# Main.net
KiCad netlist of a schematic drawn in Altium Designer
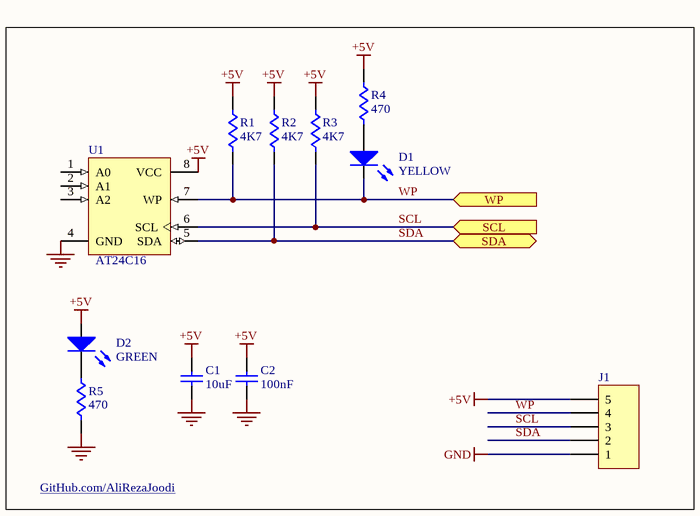
[diagram p0: Main.SchDoc]

(export (version "E")
  (design (tool "Eeschema 10.0.6"))
  (components
    (comp (ref "C1")
      (value "10uF")
      (footprint "0805")
      (description "Capacitor")
      (fields (field (name "MANUFACTURER") "Generic Components") (field (name "PUBLISHER") "Altium Limited"))
      (libsource (lib "Miscellaneous Devices") (part "Cap"))
    )
    (comp (ref "C2")
      (value "100nF")
      (footprint "0805")
      (description "Capacitor")
      (fields (field (name "MANUFACTURER") "Generic Components") (field (name "PUBLISHER") "Altium Limited"))
      (libsource (lib "Miscellaneous Devices") (part "Cap"))
    )
    (comp (ref "D1")
      (value "YELLOW")
      (footprint "0805_Diode")
      (description "Typical INFRARED GaAs LED")
      (fields (field (name "MANUFACTURER") "Generic Components") (field (name "PUBLISHER") "Altium Limited"))
      (libsource (lib "Miscellaneous Devices") (part "LED"))
    )
    (comp (ref "D2")
      (value "GREEN")
      (footprint "0805_Diode")
      (description "Typical INFRARED GaAs LED")
      (fields (field (name "MANUFACTURER") "Generic Components") (field (name "PUBLISHER") "Altium Limited"))
      (libsource (lib "Miscellaneous Devices") (part "LED"))
    )
    (comp (ref "J1")
      (value "5PIN")
      (footprint "HDR1X5")
      (description "Header, 5-Pin")
      (fields (field (name "MANUFACTURER") "Generic Components") (field (name "PUBLISHER") "Altium Limited"))
      (libsource (lib "Miscellaneous Connectors") (part "Header 5"))
    )
    (comp (ref "R1")
      (value "4K7")
      (footprint "0805")
      (description "Resistor")
      (fields (field (name "MANUFACTURER") "Generic Components") (field (name "PUBLISHER") "Altium Limited"))
      (libsource (lib "Miscellaneous Devices") (part "Res1"))
    )
    (comp (ref "R2")
      (value "4K7")
      (footprint "0805")
      (description "Resistor")
      (fields (field (name "MANUFACTURER") "Generic Components") (field (name "PUBLISHER") "Altium Limited"))
      (libsource (lib "Miscellaneous Devices") (part "Res1"))
    )
    (comp (ref "R3")
      (value "4K7")
      (footprint "0805")
      (description "Resistor")
      (fields (field (name "MANUFACTURER") "Generic Components") (field (name "PUBLISHER") "Altium Limited"))
      (libsource (lib "Miscellaneous Devices") (part "Res1"))
    )
    (comp (ref "R4")
      (value "470")
      (footprint "0805")
      (description "Resistor")
      (fields (field (name "MANUFACTURER") "Generic Components") (field (name "PUBLISHER") "Altium Limited"))
      (libsource (lib "Miscellaneous Devices") (part "Res1"))
    )
    (comp (ref "R5")
      (value "470")
      (footprint "0805")
      (description "Resistor")
      (fields (field (name "MANUFACTURER") "Generic Components") (field (name "PUBLISHER") "Altium Limited"))
      (libsource (lib "Miscellaneous Devices") (part "Res1"))
    )
    (comp (ref "U1")
      (value "AT24C16")
      (footprint "SOP127P636-8N")
      (description "1Kbit (128 x 8), 2-wire Bus Automotive Serial EEPROM with Write Protect, 2.5V, 8-Pin TSSOP, Bulk")
      (fields (field (name "PUBLISHER") "Altium Limited"))
      (libsource (lib "Atmel Memory Serial EEPROM") (part "AT24C01B-TP25-B"))
    )
  )
  (nets
    (net (code "1") (name "+5V") (class "Default")
      (node (ref "C1") (pin "2") (pinfunction "2_2") (pintype "passive"))
      (node (ref "C2") (pin "2") (pinfunction "2_2") (pintype "passive"))
      (node (ref "D2") (pin "1") (pinfunction "A_1") (pintype "passive"))
      (node (ref "J1") (pin "5") (pinfunction "5_5") (pintype "passive"))
      (node (ref "R1") (pin "2") (pinfunction "2_2") (pintype "passive"))
      (node (ref "R2") (pin "2") (pinfunction "2_2") (pintype "passive"))
      (node (ref "R3") (pin "2") (pinfunction "2_2") (pintype "passive"))
      (node (ref "R4") (pin "1") (pinfunction "1_1") (pintype "passive"))
      (node (ref "U1") (pin "8") (pinfunction "VCC_8") (pintype "power_in"))
    )
    (net (code "2") (name "/SCL") (class "Default")
      (node (ref "J1") (pin "3") (pinfunction "3_3") (pintype "passive"))
      (node (ref "R3") (pin "1") (pinfunction "1_1") (pintype "passive"))
      (node (ref "U1") (pin "6") (pinfunction "SCL_6") (pintype "input"))
    )
    (net (code "3") (name "/SDA") (class "Default")
      (node (ref "J1") (pin "2") (pinfunction "2_2") (pintype "passive"))
      (node (ref "R2") (pin "1") (pinfunction "1_1") (pintype "passive"))
      (node (ref "U1") (pin "5") (pinfunction "SDA_5") (pintype "bidirectional"))
    )
    (net (code "4") (name "/WP") (class "Default")
      (node (ref "D1") (pin "2") (pinfunction "K_2") (pintype "passive"))
      (node (ref "J1") (pin "4") (pinfunction "4_4") (pintype "passive"))
      (node (ref "R1") (pin "1") (pinfunction "1_1") (pintype "passive"))
      (node (ref "U1") (pin "7") (pinfunction "WP_7") (pintype "input"))
    )
    (net (code "5") (name "GND") (class "Default")
      (node (ref "C1") (pin "1") (pinfunction "1_1") (pintype "passive"))
      (node (ref "C2") (pin "1") (pinfunction "1_1") (pintype "passive"))
      (node (ref "J1") (pin "1") (pinfunction "1_1") (pintype "passive"))
      (node (ref "R5") (pin "2") (pinfunction "2_2") (pintype "passive"))
      (node (ref "U1") (pin "4") (pinfunction "GND_4") (pintype "power_in"))
    )
    (net (code "6") (name "Net-(D1-A)") (class "Default")
      (node (ref "D1") (pin "1") (pinfunction "A_1") (pintype "passive"))
      (node (ref "R4") (pin "2") (pinfunction "2_2") (pintype "passive"))
    )
    (net (code "7") (name "Net-(D2-K)") (class "Default")
      (node (ref "D2") (pin "2") (pinfunction "K_2") (pintype "passive"))
      (node (ref "R5") (pin "1") (pinfunction "1_1") (pintype "passive"))
    )
    (net (code "8") (name "unconnected-(U1-A0-Pad1)") (class "Default")
      (node (ref "U1") (pin "1") (pinfunction "A0_1") (pintype "input"))
    )
    (net (code "9") (name "unconnected-(U1-A1-Pad2)") (class "Default")
      (node (ref "U1") (pin "2") (pinfunction "A1_2") (pintype "input"))
    )
    (net (code "10") (name "unconnected-(U1-A2-Pad3)") (class "Default")
      (node (ref "U1") (pin "3") (pinfunction "A2_3") (pintype "input"))
    )
  )
)
